# Connectors.net
KiCad netlist of a schematic drawn in Altium Designer
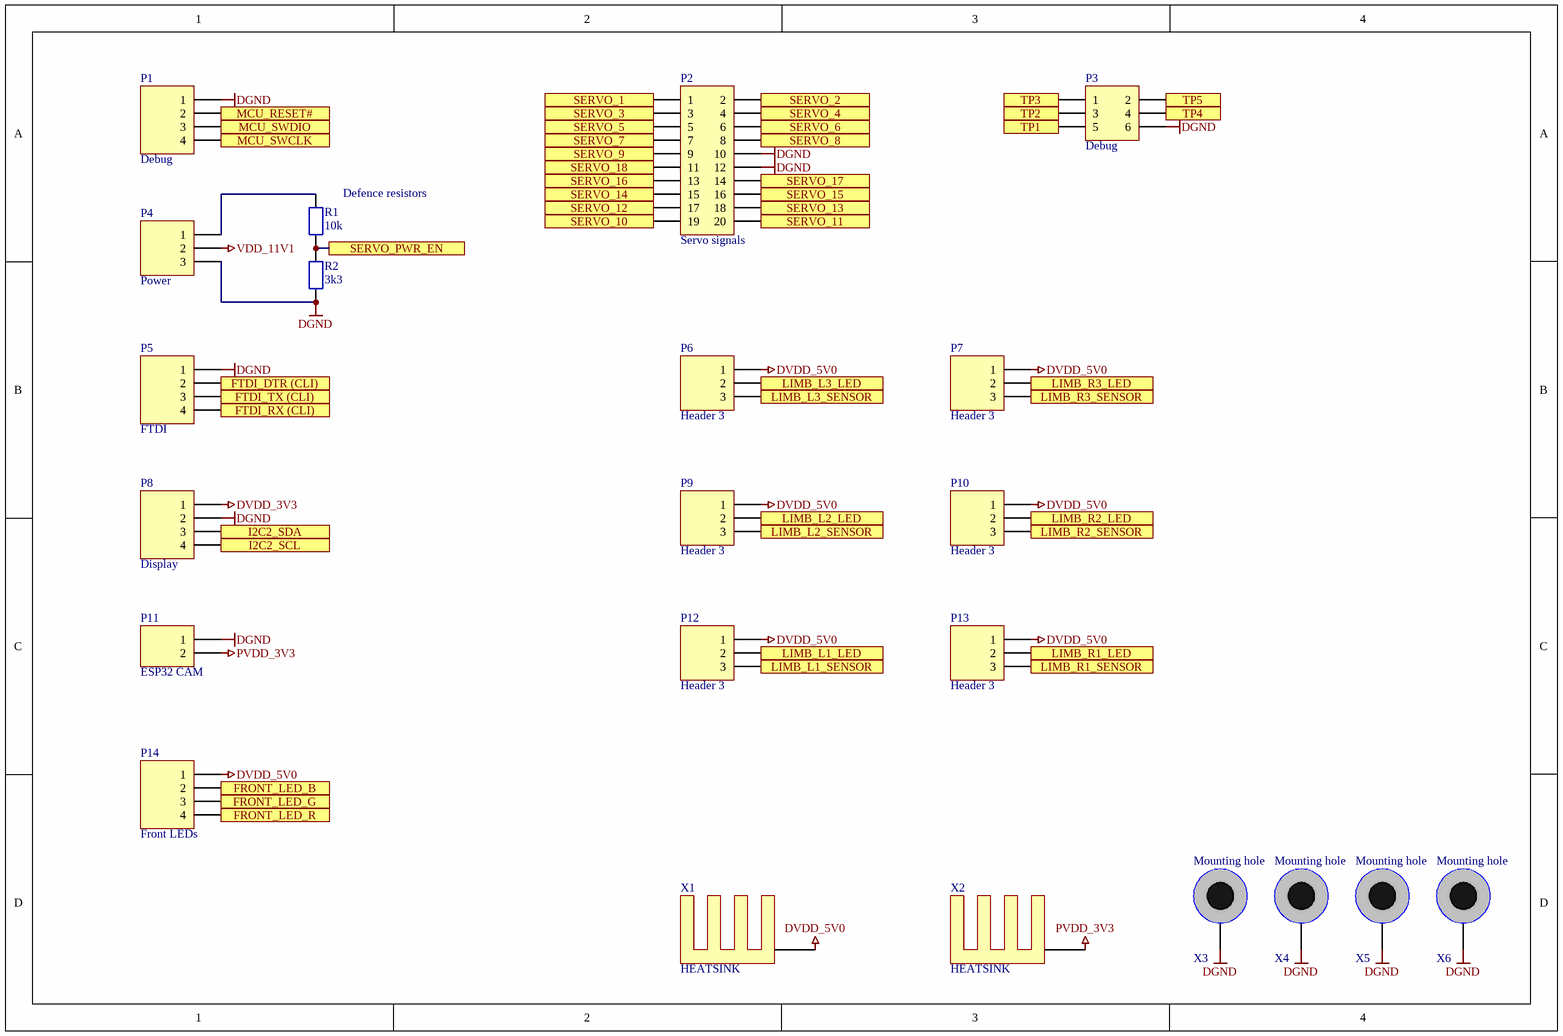
[diagram p0: Connectors.SchDoc]

(export (version "E")
  (design (tool "Eeschema 10.0.6"))
  (components
    (comp (ref "P1")
      (value "Debug")
      (footprint "PLS-4 2.54")
      (description "Header, 4-Pin")
      (fields (field (name "PUBLISHER") "Altium Limited"))
      (libsource (lib "connectors") (part "Header 4"))
    )
    (comp (ref "P2")
      (value "Servo signals")
      (footprint "IDC-20 OUTLINE")
      (description "Header, 20-Pin")
      (fields (field (name "PUBLISHER") "Altium Limited"))
      (libsource (lib "connectors") (part "Header 2x10"))
    )
    (comp (ref "P3")
      (value "Debug")
      (footprint "PLD-3 2.54")
      (description "Header, 2x3-Pin")
      (fields (field (name "PUBLISHER") "Altium Limited"))
      (libsource (lib "connectors") (part "Header 2x3"))
    )
    (comp (ref "P4")
      (value "Power")
      (footprint "PLS-3 2.54 OUTLINE")
      (description "Header, 3-Pin")
      (fields (field (name "PUBLISHER") "Altium Limited"))
      (libsource (lib "connectors") (part "Header 3"))
    )
    (comp (ref "P5")
      (value "FTDI")
      (footprint "PLS-4R 2.54")
      (description "Header, 4-Pin")
      (fields (field (name "PUBLISHER") "Altium Limited"))
      (libsource (lib "connectors") (part "Header 4"))
    )
    (comp (ref "P6")
      (value "Header 3")
      (footprint "PLS-3R 2.54")
      (description "Header, 3-Pin")
      (fields (field (name "PUBLISHER") "Altium Limited"))
      (libsource (lib "connectors") (part "Header 3"))
    )
    (comp (ref "P7")
      (value "Header 3")
      (footprint "PLS-3R 2.54")
      (description "Header, 3-Pin")
      (fields (field (name "PUBLISHER") "Altium Limited"))
      (libsource (lib "connectors") (part "Header 3"))
    )
    (comp (ref "P8")
      (value "Display")
      (footprint "PLS-4R 2.54")
      (description "Header, 4-Pin")
      (fields (field (name "PUBLISHER") "Altium Limited"))
      (libsource (lib "connectors") (part "Header 4"))
    )
    (comp (ref "P9")
      (value "Header 3")
      (footprint "PLS-3R 2.54")
      (description "Header, 3-Pin")
      (fields (field (name "PUBLISHER") "Altium Limited"))
      (libsource (lib "connectors") (part "Header 3"))
    )
    (comp (ref "P10")
      (value "Header 3")
      (footprint "PLS-3R 2.54")
      (description "Header, 3-Pin")
      (fields (field (name "PUBLISHER") "Altium Limited"))
      (libsource (lib "connectors") (part "Header 3"))
    )
    (comp (ref "P11")
      (value "ESP32 CAM")
      (footprint "PLS-2 2.54 OUTLINE")
      (description "Header, 2-Pin")
      (fields (field (name "PUBLISHER") "Altium Limited"))
      (libsource (lib "connectors") (part "Header 2"))
    )
    (comp (ref "P12")
      (value "Header 3")
      (footprint "PLS-3R 2.54")
      (description "Header, 3-Pin")
      (fields (field (name "PUBLISHER") "Altium Limited"))
      (libsource (lib "connectors") (part "Header 3"))
    )
    (comp (ref "P13")
      (value "Header 3")
      (footprint "PLS-3R 2.54")
      (description "Header, 3-Pin")
      (fields (field (name "PUBLISHER") "Altium Limited"))
      (libsource (lib "connectors") (part "Header 3"))
    )
    (comp (ref "P14")
      (value "Front LEDs")
      (footprint "PLS-4R 2.54")
      (description "Header, 4-Pin")
      (fields (field (name "PUBLISHER") "Altium Limited"))
      (libsource (lib "connectors") (part "Header 4"))
    )
    (comp (ref "R1")
      (value "10k")
      (footprint "R_0603/1608")
      (description "Resistor")
      (libsource (lib "passive") (part "Resistor"))
    )
    (comp (ref "R2")
      (value "3k3")
      (footprint "R_0603/1608")
      (description "Resistor")
      (libsource (lib "passive") (part "Resistor"))
    )
    (comp (ref "X1")
      (value "HEATSINK")
      (footprint "HEATSINK 20x14x6")
      (libsource (lib "heatsink") (part "HEATSINK"))
    )
    (comp (ref "X2")
      (value "HEATSINK")
      (footprint "HEATSINK 20x14x6")
      (libsource (lib "heatsink") (part "HEATSINK"))
    )
    (comp (ref "X3")
      (value "Mounting hole")
      (footprint "HOLE_M2_D4.0/2.5")
      (description "Hole for screw M3, outline D6")
      (libsource (lib "connectors") (part "Mounting hole"))
    )
    (comp (ref "X4")
      (value "Mounting hole")
      (footprint "HOLE_M2_D4.0/2.5")
      (description "Hole for screw M3, outline D6")
      (libsource (lib "connectors") (part "Mounting hole"))
    )
    (comp (ref "X5")
      (value "Mounting hole")
      (footprint "HOLE_M2_D4.0/2.5")
      (description "Hole for screw M3, outline D6")
      (libsource (lib "connectors") (part "Mounting hole"))
    )
    (comp (ref "X6")
      (value "Mounting hole")
      (footprint "HOLE_M2_D4.0/2.5")
      (description "Hole for screw M3, outline D6")
      (libsource (lib "connectors") (part "Mounting hole"))
    )
  )
  (nets
    (net (code "1") (name "/FRONT_LED_B") (class "Default")
      (node (ref "P14") (pin "2") (pinfunction "2_2") (pintype "passive"))
    )
    (net (code "2") (name "/FRONT_LED_G") (class "Default")
      (node (ref "P14") (pin "3") (pinfunction "3_3") (pintype "passive"))
    )
    (net (code "3") (name "/FRONT_LED_R") (class "Default")
      (node (ref "P14") (pin "4") (pinfunction "4_4") (pintype "passive"))
    )
    (net (code "4") (name "/FTDI_DTR (CLI)") (class "Default")
      (node (ref "P5") (pin "2") (pinfunction "2_2") (pintype "passive"))
    )
    (net (code "5") (name "/FTDI_RX (CLI)") (class "Default")
      (node (ref "P5") (pin "4") (pinfunction "4_4") (pintype "passive"))
    )
    (net (code "6") (name "/FTDI_TX (CLI)") (class "Default")
      (node (ref "P5") (pin "3") (pinfunction "3_3") (pintype "passive"))
    )
    (net (code "7") (name "/I2C2_SCL") (class "Default")
      (node (ref "P8") (pin "4") (pinfunction "4_4") (pintype "passive"))
    )
    (net (code "8") (name "/I2C2_SDA") (class "Default")
      (node (ref "P8") (pin "3") (pinfunction "3_3") (pintype "passive"))
    )
    (net (code "9") (name "/LIMB_L1_LED") (class "Default")
      (node (ref "P12") (pin "2") (pinfunction "2_2") (pintype "passive"))
    )
    (net (code "10") (name "/LIMB_L1_SENSOR") (class "Default")
      (node (ref "P12") (pin "3") (pinfunction "3_3") (pintype "passive"))
    )
    (net (code "11") (name "/LIMB_L2_LED") (class "Default")
      (node (ref "P9") (pin "2") (pinfunction "2_2") (pintype "passive"))
    )
    (net (code "12") (name "/LIMB_L2_SENSOR") (class "Default")
      (node (ref "P9") (pin "3") (pinfunction "3_3") (pintype "passive"))
    )
    (net (code "13") (name "/LIMB_L3_LED") (class "Default")
      (node (ref "P6") (pin "2") (pinfunction "2_2") (pintype "passive"))
    )
    (net (code "14") (name "/LIMB_L3_SENSOR") (class "Default")
      (node (ref "P6") (pin "3") (pinfunction "3_3") (pintype "passive"))
    )
    (net (code "15") (name "/LIMB_R1_LED") (class "Default")
      (node (ref "P13") (pin "2") (pinfunction "2_2") (pintype "passive"))
    )
    (net (code "16") (name "/LIMB_R1_SENSOR") (class "Default")
      (node (ref "P13") (pin "3") (pinfunction "3_3") (pintype "passive"))
    )
    (net (code "17") (name "/LIMB_R2_LED") (class "Default")
      (node (ref "P10") (pin "2") (pinfunction "2_2") (pintype "passive"))
    )
    (net (code "18") (name "/LIMB_R2_SENSOR") (class "Default")
      (node (ref "P10") (pin "3") (pinfunction "3_3") (pintype "passive"))
    )
    (net (code "19") (name "/LIMB_R3_LED") (class "Default")
      (node (ref "P7") (pin "2") (pinfunction "2_2") (pintype "passive"))
    )
    (net (code "20") (name "/LIMB_R3_SENSOR") (class "Default")
      (node (ref "P7") (pin "3") (pinfunction "3_3") (pintype "passive"))
    )
    (net (code "21") (name "/MCU_RESET#") (class "Default")
      (node (ref "P1") (pin "2") (pinfunction "2_2") (pintype "passive"))
    )
    (net (code "22") (name "/MCU_SWCLK") (class "Default")
      (node (ref "P1") (pin "4") (pinfunction "4_4") (pintype "passive"))
    )
    (net (code "23") (name "/MCU_SWDIO") (class "Default")
      (node (ref "P1") (pin "3") (pinfunction "3_3") (pintype "passive"))
    )
    (net (code "24") (name "/SERVO_1") (class "Default")
      (node (ref "P2") (pin "1") (pinfunction "1_1") (pintype "passive"))
    )
    (net (code "25") (name "/SERVO_2") (class "Default")
      (node (ref "P2") (pin "2") (pinfunction "2_2") (pintype "passive"))
    )
    (net (code "26") (name "/SERVO_3") (class "Default")
      (node (ref "P2") (pin "3") (pinfunction "3_3") (pintype "passive"))
    )
    (net (code "27") (name "/SERVO_4") (class "Default")
      (node (ref "P2") (pin "4") (pinfunction "4_4") (pintype "passive"))
    )
    (net (code "28") (name "/SERVO_5") (class "Default")
      (node (ref "P2") (pin "5") (pinfunction "5_5") (pintype "passive"))
    )
    (net (code "29") (name "/SERVO_6") (class "Default")
      (node (ref "P2") (pin "6") (pinfunction "6_6") (pintype "passive"))
    )
    (net (code "30") (name "/SERVO_7") (class "Default")
      (node (ref "P2") (pin "7") (pinfunction "7_7") (pintype "passive"))
    )
    (net (code "31") (name "/SERVO_8") (class "Default")
      (node (ref "P2") (pin "8") (pinfunction "8_8") (pintype "passive"))
    )
    (net (code "32") (name "/SERVO_9") (class "Default")
      (node (ref "P2") (pin "9") (pinfunction "9_9") (pintype "passive"))
    )
    (net (code "33") (name "/SERVO_10") (class "Default")
      (node (ref "P2") (pin "19") (pinfunction "19_19") (pintype "passive"))
    )
    (net (code "34") (name "/SERVO_11") (class "Default")
      (node (ref "P2") (pin "20") (pinfunction "20_20") (pintype "passive"))
    )
    (net (code "35") (name "/SERVO_12") (class "Default")
      (node (ref "P2") (pin "17") (pinfunction "17_17") (pintype "passive"))
    )
    (net (code "36") (name "/SERVO_13") (class "Default")
      (node (ref "P2") (pin "18") (pinfunction "18_18") (pintype "passive"))
    )
    (net (code "37") (name "/SERVO_14") (class "Default")
      (node (ref "P2") (pin "15") (pinfunction "15_15") (pintype "passive"))
    )
    (net (code "38") (name "/SERVO_15") (class "Default")
      (node (ref "P2") (pin "16") (pinfunction "16_16") (pintype "passive"))
    )
    (net (code "39") (name "/SERVO_16") (class "Default")
      (node (ref "P2") (pin "13") (pinfunction "13_13") (pintype "passive"))
    )
    (net (code "40") (name "/SERVO_17") (class "Default")
      (node (ref "P2") (pin "14") (pinfunction "14_14") (pintype "passive"))
    )
    (net (code "41") (name "/SERVO_18") (class "Default")
      (node (ref "P2") (pin "11") (pinfunction "11_11") (pintype "passive"))
    )
    (net (code "42") (name "/SERVO_PWR_EN") (class "Default")
      (node (ref "R1") (pin "1") (pintype "passive"))
      (node (ref "R2") (pin "2") (pintype "passive"))
    )
    (net (code "43") (name "/TP1") (class "Default")
      (node (ref "P3") (pin "5") (pinfunction "5_5") (pintype "passive"))
    )
    (net (code "44") (name "/TP2") (class "Default")
      (node (ref "P3") (pin "3") (pinfunction "3_3") (pintype "passive"))
    )
    (net (code "45") (name "/TP3") (class "Default")
      (node (ref "P3") (pin "1") (pinfunction "1_1") (pintype "passive"))
    )
    (net (code "46") (name "/TP4") (class "Default")
      (node (ref "P3") (pin "4") (pinfunction "4_4") (pintype "passive"))
    )
    (net (code "47") (name "/TP5") (class "Default")
      (node (ref "P3") (pin "2") (pinfunction "2_2") (pintype "passive"))
    )
    (net (code "48") (name "DGND") (class "Default")
      (node (ref "P1") (pin "1") (pinfunction "1_1") (pintype "passive"))
      (node (ref "P11") (pin "1") (pinfunction "1_1") (pintype "passive"))
      (node (ref "P2") (pin "10") (pinfunction "10_10") (pintype "passive"))
      (node (ref "P2") (pin "12") (pinfunction "12_12") (pintype "passive"))
      (node (ref "P3") (pin "6") (pinfunction "6_6") (pintype "passive"))
      (node (ref "P4") (pin "3") (pinfunction "3_3") (pintype "passive"))
      (node (ref "P5") (pin "1") (pinfunction "1_1") (pintype "passive"))
      (node (ref "P8") (pin "2") (pinfunction "2_2") (pintype "passive"))
      (node (ref "R2") (pin "1") (pintype "passive"))
      (node (ref "X3") (pin "1") (pintype "passive"))
      (node (ref "X4") (pin "1") (pintype "passive"))
      (node (ref "X5") (pin "1") (pintype "passive"))
      (node (ref "X6") (pin "1") (pintype "passive"))
    )
    (net (code "49") (name "DVDD_3V3") (class "Default")
      (node (ref "P8") (pin "1") (pinfunction "1_1") (pintype "passive"))
    )
    (net (code "50") (name "DVDD_5V0") (class "Default")
      (node (ref "P10") (pin "1") (pinfunction "1_1") (pintype "passive"))
      (node (ref "P12") (pin "1") (pinfunction "1_1") (pintype "passive"))
      (node (ref "P13") (pin "1") (pinfunction "1_1") (pintype "passive"))
      (node (ref "P14") (pin "1") (pinfunction "1_1") (pintype "passive"))
      (node (ref "P6") (pin "1") (pinfunction "1_1") (pintype "passive"))
      (node (ref "P7") (pin "1") (pinfunction "1_1") (pintype "passive"))
      (node (ref "P9") (pin "1") (pinfunction "1_1") (pintype "passive"))
      (node (ref "X1") (pin "1") (pintype "passive"))
    )
    (net (code "51") (name "Net-(P4-Pad1)") (class "Default")
      (node (ref "P4") (pin "1") (pinfunction "1_1") (pintype "passive"))
      (node (ref "R1") (pin "2") (pintype "passive"))
    )
    (net (code "52") (name "PVDD_3V3") (class "Default")
      (node (ref "P11") (pin "2") (pinfunction "2_2") (pintype "passive"))
      (node (ref "X2") (pin "1") (pintype "passive"))
    )
    (net (code "53") (name "VDD_11V1") (class "Default")
      (node (ref "P4") (pin "2") (pinfunction "2_2") (pintype "passive"))
    )
  )
)
